# Power.net
KiCad netlist of a schematic drawn in Altium Designer
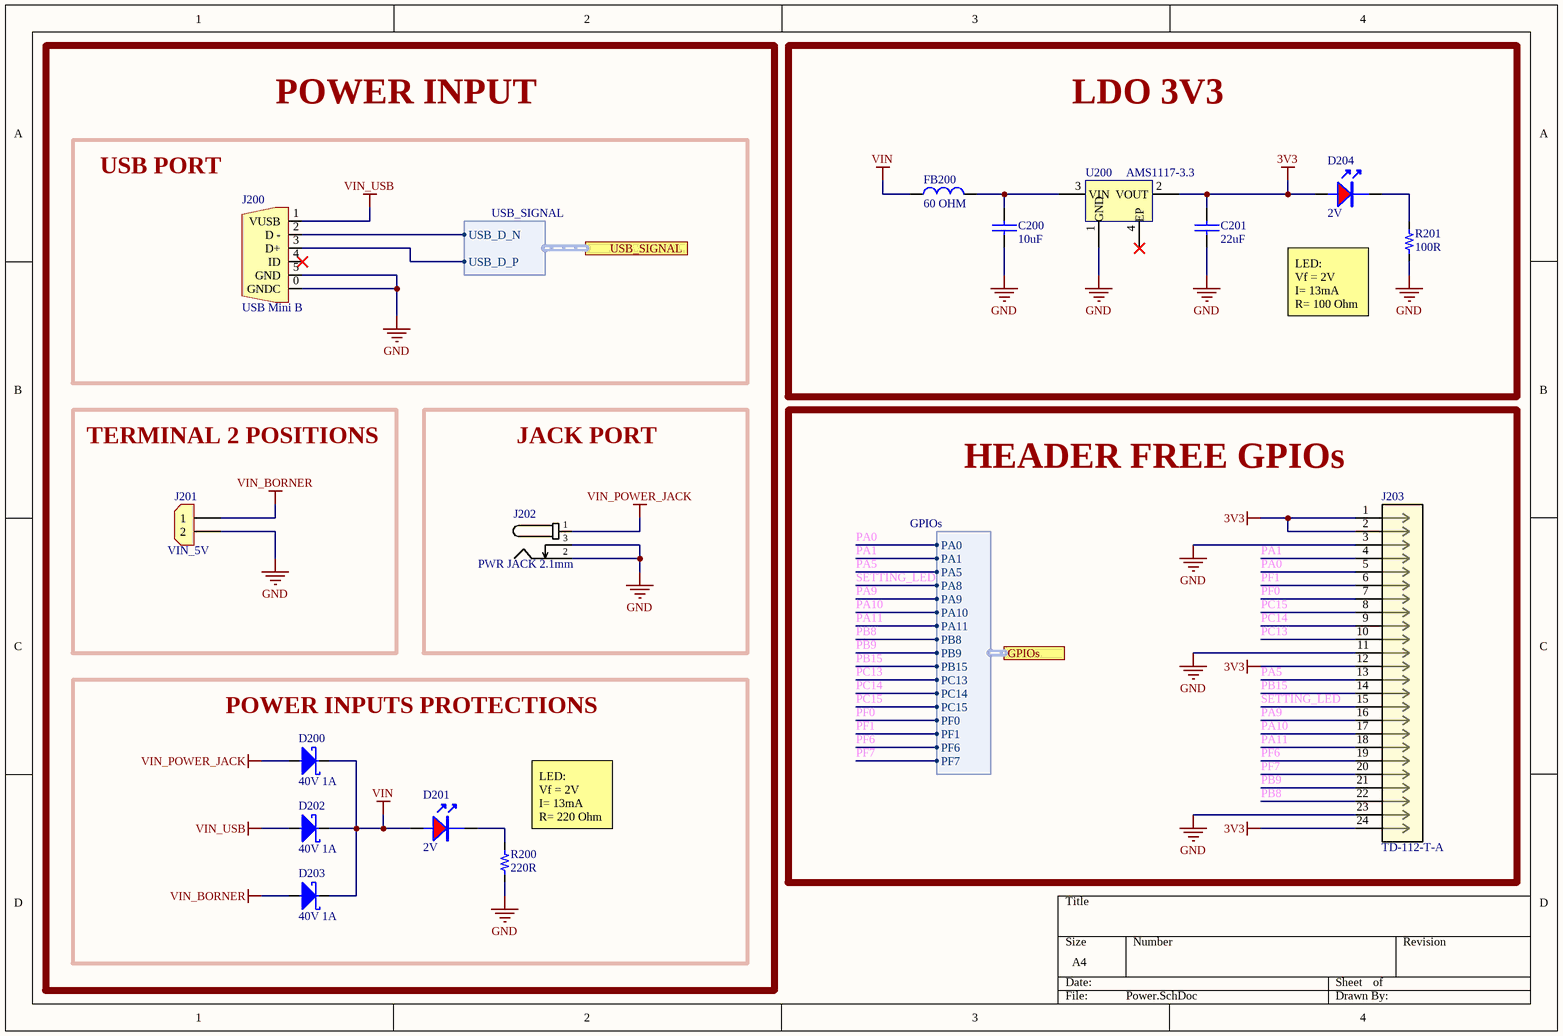
[diagram p0: Power.SchDoc]

(export (version "E")
  (design (tool "Eeschema 10.0.6"))
  (components
    (comp (ref "C200")
      (value "10uF")
      (footprint "0603_cap")
      (description "10V 10uF X5R ±10% 0603 Multilayer Ceramic Capacitors MLCC - SMD/SMT ROHS")
      (fields
        (field (name "MANUFACTURER") "CCTC")
        (field (name "MANUFACTURER PART NUMBER") "TCC0603X5R106K100CT")
      )
      (libsource (lib "shared_lib") (part "Cap_10uF_0603_10V"))
    )
    (comp (ref "C201")
      (value "22uF")
      (footprint "0603_cap")
      (description "6.3V 22uF X5R ±20% 0805 Multilayer Ceramic Capacitors MLCC - SMD/SMT ROHS")
      (fields
        (field (name "MANUFACTURER") "Samsung Electro-Mechanics")
        (field (name "MANUFACTURER PART NUMBER") "CL21A226MQQNNNE")
      )
      (libsource (lib "shared_lib") (part "Cap_22uF_0805_6V3"))
    )
    (comp (ref "D200")
      (value "40V 1A")
      (footprint "SOD_123")
      (description "DIODE SCHOTTKY 40V 1A SOD123F")
      (fields
        (field (name "MANUFACTURER") "Shanghai Prisemi Elec")
        (field (name "MANUFACTURER PART NUMBER") "PSBD1DF40V1H")
      )
      (libsource (lib "shared_lib") (part "D_Schottky_40V_1A_SOD_123F"))
    )
    (comp (ref "D201")
      (value "2V")
      (footprint "0805_LED")
      (description "LED RED CLEAR 0805 SMD")
      (fields
        (field (name "MANUFACTURER") "XINGLIGHT")
        (field (name "MANUFACTURER PART NUMBER") "XL-2012SURC")
      )
      (libsource (lib "shared_lib") (part "LED_0805_RED"))
    )
    (comp (ref "D202")
      (value "40V 1A")
      (footprint "SOD_123")
      (description "DIODE SCHOTTKY 40V 1A SOD123F")
      (fields
        (field (name "MANUFACTURER") "Shanghai Prisemi Elec")
        (field (name "MANUFACTURER PART NUMBER") "PSBD1DF40V1H")
      )
      (libsource (lib "shared_lib") (part "D_Schottky_40V_1A_SOD_123F"))
    )
    (comp (ref "D203")
      (value "40V 1A")
      (footprint "SOD_123")
      (description "DIODE SCHOTTKY 40V 1A SOD123F")
      (fields
        (field (name "MANUFACTURER") "Shanghai Prisemi Elec")
        (field (name "MANUFACTURER PART NUMBER") "PSBD1DF40V1H")
      )
      (libsource (lib "shared_lib") (part "D_Schottky_40V_1A_SOD_123F"))
    )
    (comp (ref "D204")
      (value "2V")
      (footprint "0805_LED")
      (description "LED RED CLEAR 0805 SMD")
      (fields
        (field (name "MANUFACTURER") "XINGLIGHT")
        (field (name "MANUFACTURER PART NUMBER") "XL-2012SURC")
      )
      (libsource (lib "shared_lib") (part "LED_0805_RED"))
    )
    (comp (ref "FB200")
      (value "60 OHM")
      (footprint "0603_fb")
      (description "2A 1 100mΩ 60Ω@100MHz ±25% 0603 Ferrite Beads ROHS")
      (fields
        (field (name "MANUFACTURER") "TAI-TECH")
        (field (name "MANUFACTURER PART NUMBER") "HCB1608KF-600T20")
      )
      (libsource (lib "shared_lib") (part "FB_60_0603_2A"))
    )
    (comp (ref "J200")
      (value "USB Mini B")
      (footprint "CON_5x1_SMD_miniUSB_B")
      (description "CONN RCPT USB2.0 MINI B SMD R/A")
      (fields
        (field (name "MANUFACTURER PART NUMBER") "KH-MINI-SMT-5P-Cu")
        (field (name "MANUFACTURER") "EDAC Inc.")
      )
      (libsource (lib "shared_lib") (part "Con_Mini_USB_B"))
    )
    (comp (ref "J201")
      (value "VIN_5V")
      (footprint "CON_2x1_TH_5MM")
      (description "2POS 5MM")
      (fields (field (name "MANUFACTURER") "JILN") (field (name "MANUFACTURER PART NUMBER") "JL126-50002G01"))
      (libsource (lib "shared_lib") (part "Con_2x1_TH_5mm"))
    )
    (comp (ref "J202")
      (value "PWR JACK 2.1mm")
      (footprint "CON_POWER_BARREL_2.1MM_3CONN")
      (description "CONN PWR JACK 2X5.5MM SOLDER")
      (fields (field (name "MANUFACTURER") "HCTL") (field (name "MANUFACTURER PART NUMBER") "HC-DC-005-2.0T"))
      (libsource (lib "shared_lib") (part "Con_Power_Jack_2.1mm_3pins"))
    )
    (comp (ref "J203")
      (value "TD-112-T-A")
      (footprint "CON_12X2_TH_2.54mm")
      (description "CONN HEADER VERT 24POS 2.54MM")
      (fields (field (name "MANUFACTURER") "Samtec Inc."))
      (libsource (lib "shared_lib") (part "Con_12X2_TH_2.54mm"))
    )
    (comp (ref "R200")
      (value "220R")
      (footprint "0603_res")
      (description "RES SMD 220R OHM 5% 1/10W 0603")
      (fields
        (field (name "MANUFACTURER") "FOJAN")
        (field (name "MANUFACTURER PART NUMBER") "FRC0603J221 TS")
      )
      (libsource (lib "shared_lib") (part "Res_220R_0603_1/10W"))
    )
    (comp (ref "R201")
      (value "100R")
      (footprint "0603_res")
      (description "RES SMD 100R OHM 5% 1/10W 0603")
      (fields
        (field (name "MANUFACTURER") "FOJAN")
        (field (name "MANUFACTURER PART NUMBER") "FRC0603J101 TS")
      )
      (libsource (lib "shared_lib") (part "Res_100R_0603_1/10W"))
    )
    (comp (ref "U200")
      (value "AMS1117-3.3")
      (footprint "SOT_223")
      (description "1A 60dB@(120Hz) Fixed 3.3V Positive 18V SOT-223 Linear Voltage Regulators (LDO) ROHS")
      (fields (field (name "MANUFACTURER") "UMW(Youtai Semiconductor Co., Ltd.)"))
      (libsource (lib "shared_lib") (part "LDO_3V3_1A_FIXED"))
    )
  )
  (nets
    (net (code "3") (name "/PA0") (class "Default")
      (node (ref "J203") (pin "5") (pinfunction "5_5") (pintype "passive"))
    )
    (net (code "4") (name "/PA1") (class "Default")
      (node (ref "J203") (pin "4") (pinfunction "4_4") (pintype "passive"))
    )
    (net (code "5") (name "/PA5") (class "Default")
      (node (ref "J203") (pin "13") (pinfunction "13_13") (pintype "passive"))
    )
    (net (code "6") (name "/PA9") (class "Default")
      (node (ref "J203") (pin "16") (pinfunction "16_16") (pintype "passive"))
    )
    (net (code "7") (name "/PA10") (class "Default")
      (node (ref "J203") (pin "17") (pinfunction "17_17") (pintype "passive"))
    )
    (net (code "8") (name "/PA11") (class "Default")
      (node (ref "J203") (pin "18") (pinfunction "18_18") (pintype "passive"))
    )
    (net (code "9") (name "/PB8") (class "Default")
      (node (ref "J203") (pin "22") (pinfunction "22_22") (pintype "passive"))
    )
    (net (code "10") (name "/PB9") (class "Default")
      (node (ref "J203") (pin "21") (pinfunction "21_21") (pintype "passive"))
    )
    (net (code "11") (name "/PB15") (class "Default")
      (node (ref "J203") (pin "14") (pinfunction "14_14") (pintype "passive"))
    )
    (net (code "12") (name "/PC13") (class "Default")
      (node (ref "J203") (pin "10") (pinfunction "10_10") (pintype "passive"))
    )
    (net (code "13") (name "/PC14") (class "Default")
      (node (ref "J203") (pin "9") (pinfunction "9_9") (pintype "passive"))
    )
    (net (code "14") (name "/PC15") (class "Default")
      (node (ref "J203") (pin "8") (pinfunction "8_8") (pintype "passive"))
    )
    (net (code "15") (name "/PF0") (class "Default")
      (node (ref "J203") (pin "7") (pinfunction "7_7") (pintype "passive"))
    )
    (net (code "16") (name "/PF1") (class "Default")
      (node (ref "J203") (pin "6") (pinfunction "6_6") (pintype "passive"))
    )
    (net (code "17") (name "/PF6") (class "Default")
      (node (ref "J203") (pin "19") (pinfunction "19_19") (pintype "passive"))
    )
    (net (code "18") (name "/PF7") (class "Default")
      (node (ref "J203") (pin "20") (pinfunction "20_20") (pintype "passive"))
    )
    (net (code "19") (name "/SETTING_LED") (class "Default")
      (node (ref "J203") (pin "15") (pinfunction "15_15") (pintype "passive"))
    )
    (net (code "20") (name "/USB_D_N") (class "Default")
      (node (ref "J200") (pin "2") (pinfunction "D_-_2") (pintype "passive"))
    )
    (net (code "21") (name "/USB_D_P") (class "Default")
      (node (ref "J200") (pin "3") (pinfunction "D+_3") (pintype "passive"))
    )
    (net (code "24") (name "3V3") (class "Default")
      (node (ref "C201") (pin "1") (pinfunction "1_1") (pintype "passive"))
      (node (ref "D204") (pin "1") (pinfunction "A_1") (pintype "passive"))
      (node (ref "J203") (pin "1") (pinfunction "1_1") (pintype "passive"))
      (node (ref "J203") (pin "12") (pinfunction "12_12") (pintype "passive"))
      (node (ref "J203") (pin "2") (pinfunction "2_2") (pintype "passive"))
      (node (ref "J203") (pin "24") (pinfunction "24_24") (pintype "passive"))
      (node (ref "U200") (pin "2") (pinfunction "VOUT_2") (pintype "passive"))
    )
    (net (code "25") (name "GND") (class "Default")
      (node (ref "C200") (pin "2") (pinfunction "2_2") (pintype "passive"))
      (node (ref "C201") (pin "2") (pinfunction "2_2") (pintype "passive"))
      (node (ref "J200") (pin "0") (pinfunction "GNDC_0") (pintype "passive"))
      (node (ref "J200") (pin "5") (pinfunction "GND_5") (pintype "passive"))
      (node (ref "J201") (pin "2") (pinfunction "2_2") (pintype "passive"))
      (node (ref "J202") (pin "2") (pinfunction "2_2") (pintype "passive"))
      (node (ref "J202") (pin "3") (pinfunction "3_3") (pintype "passive"))
      (node (ref "J203") (pin "11") (pinfunction "11_11") (pintype "passive"))
      (node (ref "J203") (pin "23") (pinfunction "23_23") (pintype "passive"))
      (node (ref "J203") (pin "3") (pinfunction "3_3") (pintype "passive"))
      (node (ref "R200") (pin "1") (pinfunction "1_1") (pintype "passive"))
      (node (ref "R201") (pin "1") (pinfunction "1_1") (pintype "passive"))
      (node (ref "U200") (pin "1") (pinfunction "GND_1") (pintype "passive"))
    )
    (net (code "26") (name "Net-(D201-Pad2)") (class "Default")
      (node (ref "D201") (pin "2") (pinfunction "2_2") (pintype "passive"))
      (node (ref "R200") (pin "2") (pinfunction "2_2") (pintype "passive"))
    )
    (net (code "27") (name "Net-(D204-Pad2)") (class "Default")
      (node (ref "D204") (pin "2") (pinfunction "2_2") (pintype "passive"))
      (node (ref "R201") (pin "2") (pinfunction "2_2") (pintype "passive"))
    )
    (net (code "28") (name "Net-(U200-VIN)") (class "Default")
      (node (ref "C200") (pin "1") (pinfunction "1_1") (pintype "passive"))
      (node (ref "FB200") (pin "2") (pinfunction "2_2") (pintype "passive"))
      (node (ref "U200") (pin "3") (pinfunction "VIN_3") (pintype "passive"))
    )
    (net (code "29") (name "VIN") (class "Default")
      (node (ref "D200") (pin "1") (pinfunction "1_1") (pintype "passive"))
      (node (ref "D201") (pin "1") (pinfunction "A_1") (pintype "passive"))
      (node (ref "D202") (pin "1") (pinfunction "1_1") (pintype "passive"))
      (node (ref "D203") (pin "1") (pinfunction "1_1") (pintype "passive"))
      (node (ref "FB200") (pin "1") (pinfunction "1_1") (pintype "passive"))
    )
    (net (code "30") (name "VIN_BORNER") (class "Default")
      (node (ref "D203") (pin "2") (pinfunction "2_2") (pintype "passive"))
      (node (ref "J201") (pin "1") (pinfunction "1_1") (pintype "passive"))
    )
    (net (code "31") (name "VIN_POWER_JACK") (class "Default")
      (node (ref "D200") (pin "2") (pinfunction "2_2") (pintype "passive"))
      (node (ref "J202") (pin "1") (pinfunction "1_1") (pintype "passive"))
    )
    (net (code "32") (name "VIN_USB") (class "Default")
      (node (ref "D202") (pin "2") (pinfunction "2_2") (pintype "passive"))
      (node (ref "J200") (pin "1") (pinfunction "VUSB_1") (pintype "passive"))
    )
    (net (code "33") (name "unconnected-(J200-ID-Pad4)") (class "Default")
      (node (ref "J200") (pin "4") (pinfunction "ID_4") (pintype "passive+no_connect"))
    )
    (net (code "34") (name "unconnected-(U200-EP-Pad4)") (class "Default")
      (node (ref "U200") (pin "4") (pinfunction "EP_4") (pintype "passive+no_connect"))
    )
  )
)
